# Schematic.net
KiCad netlist of a schematic drawn in Altium Designer
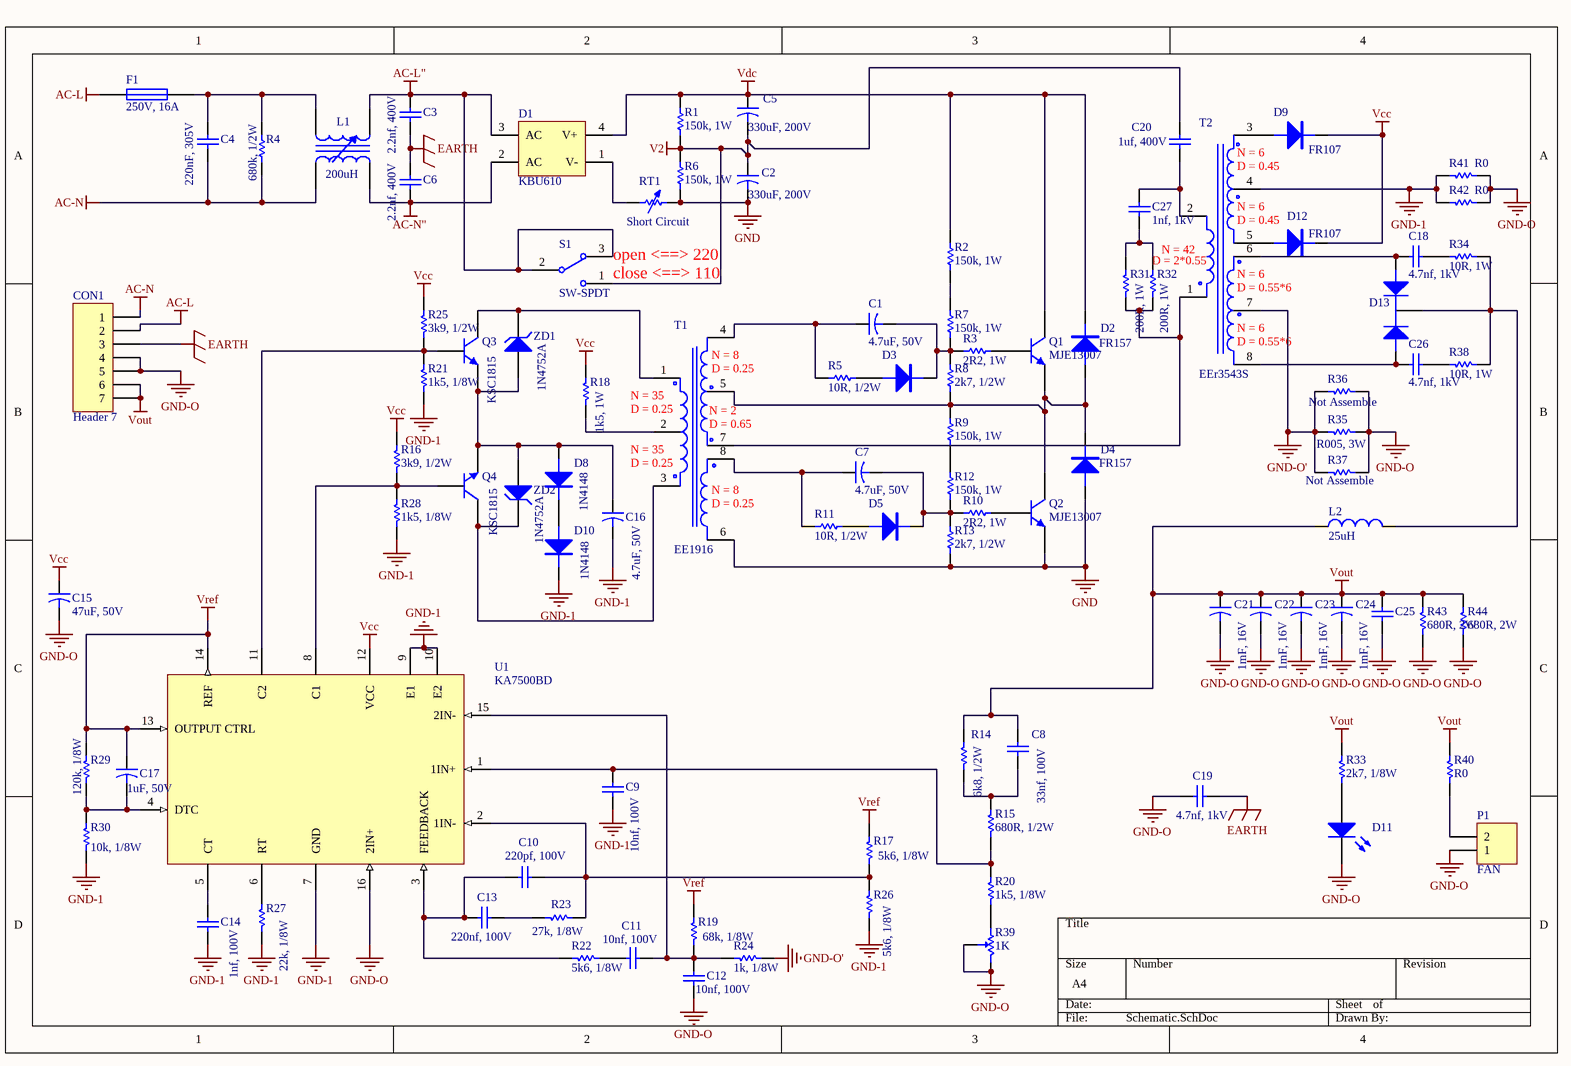
[diagram p0: Schematic.SchDoc]

(export (version "E")
  (design (tool "Eeschema 10.0.6"))
  (components
    (comp (ref "C1")
      (value "4.7uF, 50V")
      (footprint "CAP-P2.54-D6")
      (description "200V, 330uF")
      (libsource (lib "Miscellaneous Devices") (part "Cap2"))
    )
    (comp (ref "C2")
      (value "330uF, 200V")
      (footprint "C_EL_20X35")
      (description "200V, 330uF")
      (libsource (lib "Miscellaneous Devices") (part "Cap2"))
    )
    (comp (ref "C3")
      (value "2.2nf, 400V")
      (footprint "C_CER_D7C")
      (description "jn222m")
      (libsource (lib "Miscellaneous Devices") (part "Cap"))
    )
    (comp (ref "C4")
      (value "220nF, 305V")
      (footprint "CAP-pitch15")
      (description "mkp62 x2  224 k 305v")
      (libsource (lib "Miscellaneous Devices") (part "Cap"))
    )
    (comp (ref "C5")
      (value "330uF, 200V")
      (footprint "C_EL_20X35")
      (description "200V, 330uF")
      (libsource (lib "Miscellaneous Devices") (part "Cap2"))
    )
    (comp (ref "C6")
      (value "2.2nf, 400V")
      (footprint "C_CER_D7C")
      (description "jn222m")
      (libsource (lib "Miscellaneous Devices") (part "Cap"))
    )
    (comp (ref "C7")
      (value "4.7uF, 50V")
      (footprint "CAP-P2.54-D6")
      (description "200V, 330uF")
      (libsource (lib "Miscellaneous Devices") (part "Cap2"))
    )
    (comp (ref "C8")
      (value "33nf, 100V")
      (footprint "RAD0.2-1")
      (description "2A333j")
      (libsource (lib "Miscellaneous Devices") (part "Cap"))
    )
    (comp (ref "C9")
      (value "10nf, 100V")
      (footprint "RAD0.2-1")
      (description "2A103j")
      (libsource (lib "Miscellaneous Devices") (part "Cap"))
    )
    (comp (ref "C10")
      (value "220pf, 100V")
      (footprint "RAD0.2-1")
      (description "2A221j")
      (libsource (lib "Miscellaneous Devices") (part "Cap"))
    )
    (comp (ref "C11")
      (value "10nf, 100V")
      (footprint "RAD0.2-1")
      (description "2A103j")
      (libsource (lib "Miscellaneous Devices") (part "Cap"))
    )
    (comp (ref "C12")
      (value "10nf, 100V")
      (footprint "RAD0.2-1")
      (description "2A103j")
      (libsource (lib "Miscellaneous Devices") (part "Cap"))
    )
    (comp (ref "C13")
      (value "220nf, 100V")
      (footprint "RAD0.2-1")
      (description "2A223j")
      (libsource (lib "Miscellaneous Devices") (part "Cap"))
    )
    (comp (ref "C14")
      (value "1nf, 100V")
      (footprint "RAD0.2-1")
      (description "2A102j")
      (libsource (lib "Miscellaneous Devices") (part "Cap"))
    )
    (comp (ref "C15")
      (value "47uF, 50V")
      (footprint "CAP-P2.54-D6")
      (description "200V, 330uF")
      (libsource (lib "Miscellaneous Devices") (part "Cap2"))
    )
    (comp (ref "C16")
      (value "4.7uF, 50V")
      (footprint "CAP-P2.54-D6")
      (description "200V, 330uF")
      (libsource (lib "Miscellaneous Devices") (part "Cap2"))
    )
    (comp (ref "C17")
      (value "1uF, 50V")
      (footprint "CAP-P2.54-D6")
      (description "200V, 330uF")
      (libsource (lib "Miscellaneous Devices") (part "Cap2"))
    )
    (comp (ref "C18")
      (value "4.7nf, 1kV")
      (footprint "C_CER_D6B")
      (libsource (lib "Miscellaneous Devices") (part "Cap"))
    )
    (comp (ref "C19")
      (value "4.7nf, 1kV")
      (footprint "RAD0.2-1")
      (libsource (lib "Miscellaneous Devices") (part "Cap"))
    )
    (comp (ref "C20")
      (value "1uf, 400V")
      (footprint "C_PLY_22X7")
      (description "ceramic")
      (libsource (lib "Miscellaneous Devices") (part "Cap"))
    )
    (comp (ref "C21")
      (value "1mF, 16V")
      (footprint "RB.2/.6-2")
      (description "200V, 330uF")
      (libsource (lib "Miscellaneous Devices") (part "Cap2"))
    )
    (comp (ref "C22")
      (value "1mF, 16V")
      (footprint "RB.2/.6-2")
      (description "200V, 330uF")
      (libsource (lib "Miscellaneous Devices") (part "Cap2"))
    )
    (comp (ref "C23")
      (value "1mF, 16V")
      (footprint "RB.2/.6-2")
      (description "200V, 330uF")
      (libsource (lib "Miscellaneous Devices") (part "Cap2"))
    )
    (comp (ref "C24")
      (value "1mF, 16V")
      (footprint "RB.2/.6-2")
      (description "200V, 330uF")
      (libsource (lib "Miscellaneous Devices") (part "Cap2"))
    )
    (comp (ref "C25")
      (value "~")
      (footprint "C_CER_D6B")
      (libsource (lib "Miscellaneous Devices") (part "Cap"))
    )
    (comp (ref "C26")
      (value "4.7nf, 1kV")
      (footprint "C_CER_D6B")
      (libsource (lib "Miscellaneous Devices") (part "Cap"))
    )
    (comp (ref "C27")
      (value "1nf, 1kV")
      (footprint "C_CER_D6B")
      (libsource (lib "Miscellaneous Devices") (part "Cap"))
    )
    (comp (ref "CON1")
      (value "Header 7")
      (footprint "barrier-terminal-7P")
      (description "Header, 7-Pin")
      (fields (field (name "PUBLISHER") "Altium Limited"))
      (libsource (lib "Miscellaneous Connectors") (part "Header 7"))
    )
    (comp (ref "D1")
      (value "KBU610")
      (footprint "Diode-12")
      (description "35A, 1200V")
      (fields (field (name "MANUFACTURER") "HY Electronic"))
      (libsource (lib "JDEVS-SCH") (part "Bridge"))
    )
    (comp (ref "D2")
      (value "FR157")
      (footprint "D_AX05_DO15")
      (fields (field (name "MANUFACTURER") "Comchip Technology"))
      (libsource (lib "JDEVS-SCH") (part "DIODE5"))
    )
    (comp (ref "D3")
      (value "~")
      (footprint "D_AX04_DO41")
      (fields (field (name "MANUFACTURER") "Comchip Technology"))
      (libsource (lib "JDEVS-SCH") (part "DIODE5"))
    )
    (comp (ref "D4")
      (value "FR157")
      (footprint "D_AX05_DO15")
      (fields (field (name "MANUFACTURER") "Comchip Technology"))
      (libsource (lib "JDEVS-SCH") (part "DIODE5"))
    )
    (comp (ref "D5")
      (value "~")
      (footprint "D_AX04_DO41")
      (fields (field (name "MANUFACTURER") "Comchip Technology"))
      (libsource (lib "JDEVS-SCH") (part "DIODE5"))
    )
    (comp (ref "D8")
      (value "1N4148")
      (footprint "D_AX03_DO35")
      (fields (field (name "MANUFACTURER") "Comchip Technology"))
      (libsource (lib "JDEVS-SCH") (part "DIODE5"))
    )
    (comp (ref "D9")
      (value "FR107")
      (footprint "D_AX04_DO41")
      (fields (field (name "MANUFACTURER") "Comchip Technology"))
      (libsource (lib "JDEVS-SCH") (part "DIODE5"))
    )
    (comp (ref "D10")
      (value "1N4148")
      (footprint "D_AX03_DO35")
      (fields (field (name "MANUFACTURER") "Comchip Technology"))
      (libsource (lib "JDEVS-SCH") (part "DIODE5"))
    )
    (comp (ref "D11")
      (value "LED RED")
      (footprint "LED3MM")
      (description "Typical INFRARED GaAs LED")
      (libsource (lib "Miscellaneous Devices") (part "LED0"))
    )
    (comp (ref "D12")
      (value "FR107")
      (footprint "D_AX04_DO41")
      (fields (field (name "MANUFACTURER") "Comchip Technology"))
      (libsource (lib "JDEVS-SCH") (part "DIODE5"))
    )
    (comp (ref "D13")
      (value "MBR20200CT")
      (footprint "TO-220ne3")
      (fields (field (name "MANUFACTURER") "ON"))
      (libsource (lib "JDEVS-SCH") (part "Diode 3pin"))
    )
    (comp (ref "F1")
      (value "250V, 16A")
      (footprint "Fuse -10")
      (description "Fuse")
      (libsource (lib "Miscellaneous Devices") (part "Fuse 1"))
    )
    (comp (ref "L1")
      (value "200uH")
      (footprint "Trans-11")
      (fields (field (name "MANUFACTURER") "click"))
      (libsource (lib "Miscellaneous Devices") (part "Trans Adj"))
    )
    (comp (ref "L2")
      (value "25uH")
      (footprint "inductor-6")
      (description "260-04930-10E   082-10394-01    click      1929")
      (fields (field (name "MANUFACTURER") "click"))
      (libsource (lib "Miscellaneous Devices") (part "Inductor"))
    )
    (comp (ref "P1")
      (value "FAN")
      (footprint "XH_2")
      (description "Header, 2-Pin")
      (libsource (lib "Miscellaneous Connectors") (part "Header 2"))
    )
    (comp (ref "Q1")
      (value "MJE13007")
      (footprint "TO-220ne3")
      (fields (field (name "MANUFACTURER") "ON"))
      (libsource (lib "Miscellaneous Devices") (part "QNPN"))
    )
    (comp (ref "Q2")
      (value "MJE13007")
      (footprint "TO-220ne3")
      (fields (field (name "MANUFACTURER") "ON"))
      (libsource (lib "Miscellaneous Devices") (part "QNPN"))
    )
    (comp (ref "Q3")
      (value "KSC1815")
      (footprint "TO92_3B")
      (libsource (lib "Miscellaneous Devices") (part "QNPN"))
    )
    (comp (ref "Q4")
      (value "KSC1815")
      (footprint "TO92_3B")
      (libsource (lib "Miscellaneous Devices") (part "QNPN"))
    )
    (comp (ref "R1")
      (value "150k, 1W")
      (footprint "R05W_AX05")
      (description "Resistor")
      (libsource (lib "Miscellaneous Devices") (part "Res1"))
    )
    (comp (ref "R2")
      (value "150k, 1W")
      (footprint "R05W_AX05")
      (description "Resistor")
      (libsource (lib "Miscellaneous Devices") (part "Res1"))
    )
    (comp (ref "R3")
      (value "2R2, 1W")
      (footprint "R05W_AX05")
      (description "Resistor")
      (libsource (lib "Miscellaneous Devices") (part "Res1"))
    )
    (comp (ref "R4")
      (value "680k, 1/2W")
      (footprint "R05W_AX05")
      (description "Resistor")
      (libsource (lib "Miscellaneous Devices") (part "Res1"))
    )
    (comp (ref "R5")
      (value "10R, 1/2W")
      (footprint "R025W_AX04")
      (description "Resistor")
      (libsource (lib "Miscellaneous Devices") (part "Res1"))
    )
    (comp (ref "R6")
      (value "150k, 1W")
      (footprint "R05W_AX05")
      (description "Resistor")
      (libsource (lib "Miscellaneous Devices") (part "Res1"))
    )
    (comp (ref "R7")
      (value "150k, 1W")
      (footprint "R05W_AX05")
      (description "Resistor")
      (libsource (lib "Miscellaneous Devices") (part "Res1"))
    )
    (comp (ref "R8")
      (value "2k7, 1/2W")
      (footprint "R025W_AX04")
      (description "Resistor")
      (libsource (lib "Miscellaneous Devices") (part "Res1"))
    )
    (comp (ref "R9")
      (value "150k, 1W")
      (footprint "R05W_AX05")
      (description "Resistor")
      (libsource (lib "Miscellaneous Devices") (part "Res1"))
    )
    (comp (ref "R10")
      (value "2R2, 1W")
      (footprint "R05W_AX05")
      (description "Resistor")
      (libsource (lib "Miscellaneous Devices") (part "Res1"))
    )
    (comp (ref "R11")
      (value "10R, 1/2W")
      (footprint "R025W_AX04")
      (description "Resistor")
      (libsource (lib "Miscellaneous Devices") (part "Res1"))
    )
    (comp (ref "R12")
      (value "150k, 1W")
      (footprint "R05W_AX05")
      (description "Resistor")
      (libsource (lib "Miscellaneous Devices") (part "Res1"))
    )
    (comp (ref "R13")
      (value "2k7, 1/2W")
      (footprint "R025W_AX04")
      (description "Resistor")
      (libsource (lib "Miscellaneous Devices") (part "Res1"))
    )
    (comp (ref "R14")
      (value "6k8, 1/2W")
      (footprint "R025W_AX04")
      (description "Resistor")
      (libsource (lib "Miscellaneous Devices") (part "Res1"))
    )
    (comp (ref "R15")
      (value "680R, 1/2W")
      (footprint "R025W_AX04")
      (description "Resistor")
      (libsource (lib "Miscellaneous Devices") (part "Res1"))
    )
    (comp (ref "R16")
      (value "3k9, 1/2W")
      (footprint "R025W_AX04")
      (description "Resistor")
      (libsource (lib "Miscellaneous Devices") (part "Res1"))
    )
    (comp (ref "R17")
      (value "5k6, 1/8W")
      (footprint "R0125W_AX025")
      (description "Resistor")
      (libsource (lib "Miscellaneous Devices") (part "Res1"))
    )
    (comp (ref "R18")
      (value "1k5, 1W")
      (footprint "R05W_AX05")
      (description "Resistor")
      (libsource (lib "Miscellaneous Devices") (part "Res1"))
    )
    (comp (ref "R19")
      (value "68k, 1/8W")
      (footprint "R0125W_AX025")
      (description "Resistor")
      (libsource (lib "Miscellaneous Devices") (part "Res1"))
    )
    (comp (ref "R20")
      (value "1k5, 1/8W")
      (footprint "R0125W_AX025")
      (description "Resistor")
      (libsource (lib "Miscellaneous Devices") (part "Res1"))
    )
    (comp (ref "R21")
      (value "1k5, 1/8W")
      (footprint "R0125W_AX025")
      (description "Resistor")
      (libsource (lib "Miscellaneous Devices") (part "Res1"))
    )
    (comp (ref "R22")
      (value "5k6, 1/8W")
      (footprint "R0125W_AX025")
      (description "Resistor")
      (libsource (lib "Miscellaneous Devices") (part "Res1"))
    )
    (comp (ref "R23")
      (value "27k, 1/8W")
      (footprint "R0125W_AX025")
      (description "Resistor")
      (libsource (lib "Miscellaneous Devices") (part "Res1"))
    )
    (comp (ref "R24")
      (value "1k, 1/8W")
      (footprint "R0125W_AX025")
      (description "Resistor")
      (libsource (lib "Miscellaneous Devices") (part "Res1"))
    )
    (comp (ref "R25")
      (value "3k9, 1/2W")
      (footprint "R025W_AX04")
      (description "Resistor")
      (libsource (lib "Miscellaneous Devices") (part "Res1"))
    )
    (comp (ref "R26")
      (value "5k6, 1/8W")
      (footprint "R0125W_AX025")
      (description "Resistor")
      (libsource (lib "Miscellaneous Devices") (part "Res1"))
    )
    (comp (ref "R27")
      (value "22k, 1/8W")
      (footprint "R0125W_AX025")
      (description "Resistor")
      (libsource (lib "Miscellaneous Devices") (part "Res1"))
    )
    (comp (ref "R28")
      (value "1k5, 1/8W")
      (footprint "R0125W_AX025")
      (description "Resistor")
      (libsource (lib "Miscellaneous Devices") (part "Res1"))
    )
    (comp (ref "R29")
      (value "120k, 1/8W")
      (footprint "R0125W_AX025")
      (description "Resistor")
      (libsource (lib "Miscellaneous Devices") (part "Res1"))
    )
    (comp (ref "R30")
      (value "10k, 1/8W")
      (footprint "R0125W_AX025")
      (description "Resistor")
      (libsource (lib "Miscellaneous Devices") (part "Res1"))
    )
    (comp (ref "R31")
      (value "200R, 1W")
      (footprint "R1W_AX06")
      (description "Resistor")
      (libsource (lib "Miscellaneous Devices") (part "Res1"))
    )
    (comp (ref "R32")
      (value "200R, 1W")
      (footprint "R1W_AX06")
      (description "Resistor")
      (libsource (lib "Miscellaneous Devices") (part "Res1"))
    )
    (comp (ref "R33")
      (value "2k7, 1/8W")
      (footprint "R0125W_AX025")
      (description "Resistor")
      (libsource (lib "Miscellaneous Devices") (part "Res1"))
    )
    (comp (ref "R34")
      (value "10R, 1W")
      (footprint "R05W_AX05")
      (description "Resistor")
      (libsource (lib "Miscellaneous Devices") (part "Res1"))
    )
    (comp (ref "R35")
      (value "R005, 3W")
      (footprint "J10MM")
      (description "Resistor")
      (libsource (lib "Miscellaneous Devices") (part "Res1"))
    )
    (comp (ref "R36")
      (value "Not Assemble")
      (footprint "J10MM")
      (description "Resistor")
      (libsource (lib "Miscellaneous Devices") (part "Res1"))
    )
    (comp (ref "R37")
      (value "Not Assemble")
      (footprint "J10MM")
      (description "Resistor")
      (libsource (lib "Miscellaneous Devices") (part "Res1"))
    )
    (comp (ref "R38")
      (value "10R, 1W")
      (footprint "R05W_AX05")
      (description "Resistor")
      (libsource (lib "Miscellaneous Devices") (part "Res1"))
    )
    (comp (ref "R39")
      (value "1K")
      (footprint "Pot 00")
      (description "Variable Resistor")
      (fields (field (name "DESIGNER") "Saeid Jorablo"))
      (libsource (lib "My Library") (part "Resistor Variable"))
    )
    (comp (ref "R40")
      (value "R0")
      (footprint "J10MM")
      (description "Resistor")
      (libsource (lib "Miscellaneous Devices") (part "Res1"))
    )
    (comp (ref "R41")
      (value "R0")
      (footprint "J7P6MM")
      (description "Resistor")
      (libsource (lib "Miscellaneous Devices") (part "Res1"))
    )
    (comp (ref "R42")
      (value "R0")
      (footprint "J7P6MM")
      (description "Resistor")
      (libsource (lib "Miscellaneous Devices") (part "Res1"))
    )
    (comp (ref "R43")
      (value "680R, 2W")
      (footprint "R1W_AX06")
      (description "NA")
      (libsource (lib "Miscellaneous Devices") (part "Res1"))
    )
    (comp (ref "R44")
      (value "680R, 2W")
      (footprint "R1W_AX06")
      (description "Resistor")
      (libsource (lib "Miscellaneous Devices") (part "Res1"))
    )
    (comp (ref "RT1")
      (value "Short Circuit")
      (footprint "J7P6MM")
      (libsource (lib "Miscellaneous Devices") (part "Res Adj1"))
    )
    (comp (ref "S1")
      (value "SW-SPDT")
      (footprint "Switch - SPDT")
      (description "SPDT Subminiature Toggle Switch, Right Angle Mounting, Vertical Actuation")
      (fields (field (name "PUBLISHER") "Altium Limited"))
      (libsource (lib "Miscellaneous Devices") (part "SW-SPDT"))
    )
    (comp (ref "T1")
      (value "EE1916")
      (footprint "EE1916-3")
      (libsource (lib "JDEVS-SCH") (part "Transformers 78253 Series_1"))
    )
    (comp (ref "T2")
      (value "EEr3543S")
      (footprint "EFD30_12")
      (libsource (lib "JDEVS-SCH") (part "Transformers 78253 Series_2"))
    )
    (comp (ref "U1")
      (value "KA7500BD")
      (footprint "Dip-16pin")
      (description "TEXAS INSTRUMENTS - TL494CN - VOLTAGE MODE PWM CONTROLLER, 40V, 16-DIP")
      (fields
        (field (name "MANUFACTURER") "Texas Instruments")
        (field (name "MANUFACTURER PART NUMBER") "TL494CN")
      )
      (libsource (lib "JDEVS-SCH") (part "KA7500BD"))
    )
    (comp (ref "ZD1")
      (value "1N4752A")
      (footprint "Diode 1W")
      (description "25V Zener Diode")
      (libsource (lib "Miscellaneous Devices") (part "D Zener"))
    )
    (comp (ref "ZD2")
      (value "1N4752A")
      (footprint "Diode 1W")
      (description "25V Zener Diode")
      (libsource (lib "Miscellaneous Devices") (part "D Zener"))
    )
  )
  (nets
    (net (code "1") (name "AC-L") (class "Default")
      (node (ref "CON1") (pin "2") (pinfunction "2_2") (pintype "passive"))
      (node (ref "F1") (pin "2") (pinfunction "2_2") (pintype "passive"))
    )
    (net (code "2") (name "AC-L\"") (class "Default")
      (node (ref "C3") (pin "1") (pinfunction "1_1") (pintype "passive"))
      (node (ref "D1") (pin "3") (pinfunction "AC_3") (pintype "passive"))
      (node (ref "L1") (pin "2") (pinfunction "2_2") (pintype "passive"))
      (node (ref "S1") (pin "2") (pinfunction "2_2") (pintype "passive"))
      (node (ref "S1") (pin "3") (pinfunction "3_3") (pintype "passive"))
    )
    (net (code "3") (name "AC-N") (class "Default")
      (node (ref "C4") (pin "2") (pinfunction "2_2") (pintype "passive"))
      (node (ref "CON1") (pin "1") (pinfunction "1_1") (pintype "passive"))
      (node (ref "L1") (pin "1") (pinfunction "3_1") (pintype "passive"))
      (node (ref "R4") (pin "2") (pinfunction "2_2") (pintype "passive"))
    )
    (net (code "4") (name "AC-N\"") (class "Default")
      (node (ref "C6") (pin "2") (pinfunction "2_2") (pintype "passive"))
      (node (ref "D1") (pin "2") (pinfunction "AC_2") (pintype "passive"))
      (node (ref "L1") (pin "3") (pinfunction "1_3") (pintype "passive"))
    )
    (net (code "5") (name "EARTH") (class "Default")
      (node (ref "C19") (pin "2") (pinfunction "2_2") (pintype "passive"))
      (node (ref "C3") (pin "2") (pinfunction "2_2") (pintype "passive"))
      (node (ref "C6") (pin "1") (pinfunction "1_1") (pintype "passive"))
      (node (ref "CON1") (pin "3") (pinfunction "3_3") (pintype "passive"))
    )
    (net (code "6") (name "GND") (class "Default")
      (node (ref "C2") (pin "2") (pinfunction "2_2") (pintype "passive"))
      (node (ref "D4") (pin "1") (pinfunction "1_1") (pintype "passive"))
      (node (ref "Q2") (pin "1") (pinfunction "E_1") (pintype "passive"))
      (node (ref "R13") (pin "2") (pinfunction "2_2") (pintype "passive"))
      (node (ref "R6") (pin "2") (pinfunction "2_2") (pintype "passive"))
      (node (ref "RT1") (pin "2") (pinfunction "2_2") (pintype "passive"))
      (node (ref "T1") (pin "6") (pinfunction "6_6") (pintype "passive"))
    )
    (net (code "7") (name "GND-1") (class "Default")
      (node (ref "C14") (pin "2") (pinfunction "2_2") (pintype "passive"))
      (node (ref "C16") (pin "2") (pinfunction "2_2") (pintype "passive"))
      (node (ref "C9") (pin "2") (pinfunction "2_2") (pintype "passive"))
      (node (ref "D10") (pin "2") (pinfunction "2_2") (pintype "passive"))
      (node (ref "R21") (pin "2") (pinfunction "2_2") (pintype "passive"))
      (node (ref "R26") (pin "2") (pinfunction "2_2") (pintype "passive"))
      (node (ref "R27") (pin "2") (pinfunction "2_2") (pintype "passive"))
      (node (ref "R28") (pin "2") (pinfunction "2_2") (pintype "passive"))
      (node (ref "R30") (pin "2") (pinfunction "2_2") (pintype "passive"))
      (node (ref "R41") (pin "2") (pinfunction "2_2") (pintype "passive"))
      (node (ref "R42") (pin "2") (pinfunction "2_2") (pintype "passive"))
      (node (ref "T2") (pin "4") (pinfunction "4_4") (pintype "passive"))
      (node (ref "U1") (pin "10") (pinfunction "E2_10") (pintype "passive"))
      (node (ref "U1") (pin "7") (pinfunction "GND_7") (pintype "power_in"))
      (node (ref "U1") (pin "9") (pinfunction "E1_9") (pintype "passive"))
    )
    (net (code "8") (name "GND-O") (class "Default")
      (node (ref "C12") (pin "1") (pinfunction "1_1") (pintype "passive"))
      (node (ref "C15") (pin "2") (pinfunction "2_2") (pintype "passive"))
      (node (ref "C19") (pin "1") (pinfunction "1_1") (pintype "passive"))
      (node (ref "C21") (pin "2") (pinfunction "2_2") (pintype "passive"))
      (node (ref "C22") (pin "2") (pinfunction "2_2") (pintype "passive"))
      (node (ref "C23") (pin "2") (pinfunction "2_2") (pintype "passive"))
      (node (ref "C24") (pin "2") (pinfunction "2_2") (pintype "passive"))
      (node (ref "C25") (pin "2") (pinfunction "2_2") (pintype "passive"))
      (node (ref "CON1") (pin "4") (pinfunction "4_4") (pintype "passive"))
      (node (ref "CON1") (pin "5") (pinfunction "5_5") (pintype "passive"))
      (node (ref "D11") (pin "2") (pinfunction "K_2") (pintype "passive"))
      (node (ref "P1") (pin "1") (pinfunction "1_1") (pintype "passive"))
      (node (ref "R35") (pin "2") (pinfunction "2_2") (pintype "passive"))
      (node (ref "R36") (pin "1") (pinfunction "1_1") (pintype "passive"))
      (node (ref "R37") (pin "2") (pinfunction "2_2") (pintype "passive"))
      (node (ref "R39") (pin "1") (pinfunction "CCW_1") (pintype "passive"))
      (node (ref "R39") (pin "3") (pinfunction "Setpoint_3") (pintype "passive"))
      (node (ref "R41") (pin "1") (pinfunction "1_1") (pintype "passive"))
      (node (ref "R42") (pin "1") (pinfunction "1_1") (pintype "passive"))
      (node (ref "R43") (pin "1") (pinfunction "1_1") (pintype "passive"))
      (node (ref "R44") (pin "1") (pinfunction "1_1") (pintype "passive"))
      (node (ref "U1") (pin "16") (pinfunction "2IN+_16") (pintype "input"))
    )
    (net (code "9") (name "GND-O'") (class "Default")
      (node (ref "R24") (pin "2") (pinfunction "2_2") (pintype "passive"))
      (node (ref "R35") (pin "1") (pinfunction "1_1") (pintype "passive"))
      (node (ref "R36") (pin "2") (pinfunction "2_2") (pintype "passive"))
      (node (ref "R37") (pin "1") (pinfunction "1_1") (pintype "passive"))
      (node (ref "T2") (pin "7") (pinfunction "7_7") (pintype "passive"))
    )
    (net (code "10") (name "Net-(C1-Pad1)") (class "Default")
      (node (ref "C1") (pin "1") (pinfunction "1_1") (pintype "passive"))
      (node (ref "R5") (pin "2") (pinfunction "2_2") (pintype "passive"))
      (node (ref "T1") (pin "4") (pinfunction "4_4") (pintype "passive"))
    )
    (net (code "11") (name "Net-(C1-Pad2)") (class "Default")
      (node (ref "C1") (pin "2") (pinfunction "2_2") (pintype "passive"))
      (node (ref "D3") (pin "2") (pinfunction "2_2") (pintype "passive"))
      (node (ref "R3") (pin "2") (pinfunction "2_2") (pintype "passive"))
      (node (ref "R7") (pin "2") (pinfunction "2_2") (pintype "passive"))
      (node (ref "R8") (pin "1") (pinfunction "1_1") (pintype "passive"))
    )
    (net (code "12") (name "Net-(C4-Pad1)") (class "Default")
      (node (ref "C4") (pin "1") (pinfunction "1_1") (pintype "passive"))
      (node (ref "F1") (pin "1") (pinfunction "1_1") (pintype "passive"))
      (node (ref "L1") (pin "4") (pinfunction "4_4") (pintype "passive"))
      (node (ref "R4") (pin "1") (pinfunction "1_1") (pintype "passive"))
    )
    (net (code "13") (name "Net-(C7-Pad1)") (class "Default")
      (node (ref "C7") (pin "1") (pinfunction "1_1") (pintype "passive"))
      (node (ref "R11") (pin "2") (pinfunction "2_2") (pintype "passive"))
      (node (ref "T1") (pin "8") (pinfunction "8_8") (pintype "passive"))
    )
    (net (code "14") (name "Net-(C7-Pad2)") (class "Default")
      (node (ref "C7") (pin "2") (pinfunction "2_2") (pintype "passive"))
      (node (ref "D5") (pin "2") (pinfunction "2_2") (pintype "passive"))
      (node (ref "R10") (pin "2") (pinfunction "2_2") (pintype "passive"))
      (node (ref "R12") (pin "2") (pinfunction "2_2") (pintype "passive"))
      (node (ref "R13") (pin "1") (pinfunction "1_1") (pintype "passive"))
    )
    (net (code "15") (name "Net-(C8-Pad2)") (class "Default")
      (node (ref "C8") (pin "2") (pinfunction "2_2") (pintype "passive"))
      (node (ref "R14") (pin "2") (pinfunction "2_2") (pintype "passive"))
      (node (ref "R15") (pin "1") (pinfunction "1_1") (pintype "passive"))
    )
    (net (code "16") (name "Net-(C11-Pad1)") (class "Default")
      (node (ref "C11") (pin "1") (pinfunction "1_1") (pintype "passive"))
      (node (ref "R22") (pin "2") (pinfunction "2_2") (pintype "passive"))
    )
    (net (code "17") (name "Net-(C13-Pad2)") (class "Default")
      (node (ref "C13") (pin "2") (pinfunction "2_2") (pintype "passive"))
      (node (ref "R23") (pin "1") (pinfunction "1_1") (pintype "passive"))
    )
    (net (code "18") (name "Net-(C18-Pad1)") (class "Default")
      (node (ref "C18") (pin "1") (pinfunction "1_1") (pintype "passive"))
      (node (ref "R34") (pin "2") (pinfunction "2_2") (pintype "passive"))
    )
    (net (code "19") (name "Net-(C18-Pad2)") (class "Default")
      (node (ref "C18") (pin "2") (pinfunction "2_2") (pintype "passive"))
      (node (ref "D13") (pin "3") (pinfunction "3_3") (pintype "passive"))
      (node (ref "T2") (pin "6") (pinfunction "6_6") (pintype "passive"))
    )
    (net (code "20") (name "Net-(C20-Pad2)") (class "Default")
      (node (ref "C20") (pin "2") (pinfunction "2_2") (pintype "passive"))
      (node (ref "C27") (pin "1") (pinfunction "1_1") (pintype "passive"))
      (node (ref "T2") (pin "2") (pinfunction "2_2") (pintype "passive"))
    )
    (net (code "21") (name "Net-(C26-Pad1)") (class "Default")
      (node (ref "C26") (pin "1") (pinfunction "1_1") (pintype "passive"))
      (node (ref "D13") (pin "1") (pinfunction "1_1") (pintype "passive"))
      (node (ref "T2") (pin "8") (pinfunction "8_8") (pintype "passive"))
    )
    (net (code "22") (name "Net-(C26-Pad2)") (class "Default")
      (node (ref "C26") (pin "2") (pinfunction "2_2") (pintype "passive"))
      (node (ref "R38") (pin "2") (pinfunction "2_2") (pintype "passive"))
    )
    (net (code "23") (name "Net-(C27-Pad2)") (class "Default")
      (node (ref "C27") (pin "2") (pinfunction "2_2") (pintype "passive"))
      (node (ref "R31") (pin "2") (pinfunction "2_2") (pintype "passive"))
      (node (ref "R32") (pin "2") (pinfunction "2_2") (pintype "passive"))
    )
    (net (code "24") (name "Net-(D1-V-)") (class "Default")
      (node (ref "D1") (pin "1") (pinfunction "V-_1") (pintype "passive"))
      (node (ref "RT1") (pin "1") (pinfunction "1_1") (pintype "passive"))
    )
    (net (code "25") (name "Net-(D3-Pad1)") (class "Default")
      (node (ref "D3") (pin "1") (pinfunction "1_1") (pintype "passive"))
      (node (ref "R5") (pin "1") (pinfunction "1_1") (pintype "passive"))
    )
    (net (code "26") (name "Net-(D5-Pad1)") (class "Default")
      (node (ref "D5") (pin "1") (pinfunction "1_1") (pintype "passive"))
      (node (ref "R11") (pin "1") (pinfunction "1_1") (pintype "passive"))
    )
    (net (code "27") (name "Net-(D9-Pad1)") (class "Default")
      (node (ref "D9") (pin "1") (pinfunction "1_1") (pintype "passive"))
      (node (ref "T2") (pin "3") (pinfunction "3_3") (pintype "passive"))
    )
    (net (code "28") (name "Net-(D10-Pad1)") (class "Default")
      (node (ref "D10") (pin "1") (pinfunction "1_1") (pintype "passive"))
      (node (ref "D8") (pin "2") (pinfunction "2_2") (pintype "passive"))
    )
    (net (code "29") (name "Net-(D11-A)") (class "Default")
      (node (ref "D11") (pin "1") (pinfunction "A_1") (pintype "passive"))
      (node (ref "R33") (pin "2") (pinfunction "2_2") (pintype "passive"))
    )
    (net (code "30") (name "Net-(D12-Pad1)") (class "Default")
      (node (ref "D12") (pin "1") (pinfunction "1_1") (pintype "passive"))
      (node (ref "T2") (pin "5") (pinfunction "5_5") (pintype "passive"))
    )
    (net (code "31") (name "Net-(D13-Pad2)") (class "Default")
      (node (ref "D13") (pin "2") (pinfunction "2_2") (pintype "passive"))
      (node (ref "L2") (pin "2") (pinfunction "2_2") (pintype "passive"))
      (node (ref "R34") (pin "1") (pinfunction "1_1") (pintype "passive"))
      (node (ref "R38") (pin "1") (pinfunction "1_1") (pintype "passive"))
    )
    (net (code "32") (name "Net-(P1-Pad2)") (class "Default")
      (node (ref "P1") (pin "2") (pinfunction "2_2") (pintype "passive"))
      (node (ref "R40") (pin "1") (pinfunction "1_1") (pintype "passive"))
    )
    (net (code "33") (name "Net-(Q1-B)") (class "Default")
      (node (ref "Q1") (pin "3") (pinfunction "B_3") (pintype "passive"))
      (node (ref "R3") (pin "1") (pinfunction "1_1") (pintype "passive"))
    )
    (net (code "34") (name "Net-(Q1-E)") (class "Default")
      (node (ref "D2") (pin "1") (pinfunction "1_1") (pintype "passive"))
      (node (ref "D4") (pin "2") (pinfunction "2_2") (pintype "passive"))
      (node (ref "Q1") (pin "1") (pinfunction "E_1") (pintype "passive"))
      (node (ref "Q2") (pin "2") (pinfunction "C_2") (pintype "passive"))
      (node (ref "R8") (pin "2") (pinfunction "2_2") (pintype "passive"))
      (node (ref "R9") (pin "1") (pinfunction "1_1") (pintype "passive"))
      (node (ref "T1") (pin "5") (pinfunction "5_5") (pintype "passive"))
    )
    (net (code "35") (name "Net-(Q2-B)") (class "Default")
      (node (ref "Q2") (pin "3") (pinfunction "B_3") (pintype "passive"))
      (node (ref "R10") (pin "1") (pinfunction "1_1") (pintype "passive"))
    )
    (net (code "36") (name "Net-(Q3-B)") (class "Default")
      (node (ref "Q3") (pin "3") (pinfunction "B_3") (pintype "passive"))
      (node (ref "R21") (pin "1") (pinfunction "1_1") (pintype "passive"))
      (node (ref "R25") (pin "2") (pinfunction "2_2") (pintype "passive"))
      (node (ref "U1") (pin "11") (pinfunction "C2_11") (pintype "passive"))
    )
    (net (code "37") (name "Net-(Q3-C)") (class "Default")
      (node (ref "Q3") (pin "2") (pinfunction "C_2") (pintype "passive"))
      (node (ref "T1") (pin "1") (pinfunction "1_1") (pintype "passive"))
      (node (ref "ZD1") (pin "2") (pinfunction "K_2") (pintype "passive"))
    )
    (net (code "38") (name "Net-(Q3-E)") (class "Default")
      (node (ref "C16") (pin "1") (pinfunction "1_1") (pintype "passive"))
      (node (ref "D8") (pin "1") (pinfunction "1_1") (pintype "passive"))
      (node (ref "Q3") (pin "1") (pinfunction "E_1") (pintype "passive"))
      (node (ref "Q4") (pin "1") (pinfunction "E_1") (pintype "passive"))
      (node (ref "ZD1") (pin "1") (pinfunction "A_1") (pintype "passive"))
      (node (ref "ZD2") (pin "1") (pinfunction "A_1") (pintype "passive"))
    )
    (net (code "39") (name "Net-(Q4-B)") (class "Default")
      (node (ref "Q4") (pin "3") (pinfunction "B_3") (pintype "passive"))
      (node (ref "R16") (pin "2") (pinfunction "2_2") (pintype "passive"))
      (node (ref "R28") (pin "1") (pinfunction "1_1") (pintype "passive"))
      (node (ref "U1") (pin "8") (pinfunction "C1_8") (pintype "passive"))
    )
    (net (code "40") (name "Net-(Q4-C)") (class "Default")
      (node (ref "Q4") (pin "2") (pinfunction "C_2") (pintype "passive"))
      (node (ref "T1") (pin "3") (pinfunction "3_3") (pintype "passive"))
      (node (ref "ZD2") (pin "2") (pinfunction "K_2") (pintype "passive"))
    )
    (net (code "41") (name "Net-(R2-Pad2)") (class "Default")
      (node (ref "R2") (pin "2") (pinfunction "2_2") (pintype "passive"))
      (node (ref "R7") (pin "1") (pinfunction "1_1") (pintype "passive"))
    )
    (net (code "42") (name "Net-(R12-Pad1)") (class "Default")
      (node (ref "R12") (pin "1") (pinfunction "1_1") (pintype "passive"))
      (node (ref "R9") (pin "2") (pinfunction "2_2") (pintype "passive"))
    )
    (net (code "43") (name "Net-(R18-Pad1)") (class "Default")
      (node (ref "R18") (pin "1") (pinfunction "1_1") (pintype "passive"))
      (node (ref "T1") (pin "2") (pinfunction "2_2") (pintype "passive"))
    )
    (net (code "44") (name "Net-(R31-Pad1)") (class "Default")
      (node (ref "R31") (pin "1") (pinfunction "1_1") (pintype "passive"))
      (node (ref "R32") (pin "1") (pinfunction "1_1") (pintype "passive"))
      (node (ref "T1") (pin "7") (pinfunction "7_7") (pintype "passive"))
      (node (ref "T2") (pin "1") (pinfunction "1_1") (pintype "passive"))
    )
    (net (code "45") (name "Net-(R39-CW)") (class "Default")
      (node (ref "R20") (pin "1") (pinfunction "1_1") (pintype "passive"))
      (node (ref "R39") (pin "2") (pinfunction "CW_2") (pintype "passive"))
    )
    (net (code "46") (name "Net-(U1-1IN+)") (class "Default")
      (node (ref "C9") (pin "1") (pinfunction "1_1") (pintype "passive"))
      (node (ref "R15") (pin "2") (pinfunction "2_2") (pintype "passive"))
      (node (ref "R20") (pin "2") (pinfunction "2_2") (pintype "passive"))
      (node (ref "U1") (pin "1") (pinfunction "1IN+_1") (pintype "input"))
    )
    (net (code "47") (name "Net-(U1-1IN-)") (class "Default")
      (node (ref "C10") (pin "2") (pinfunction "2_2") (pintype "passive"))
      (node (ref "R17") (pin "2") (pinfunction "2_2") (pintype "passive"))
      (node (ref "R23") (pin "2") (pinfunction "2_2") (pintype "passive"))
      (node (ref "R26") (pin "1") (pinfunction "1_1") (pintype "passive"))
      (node (ref "U1") (pin "2") (pinfunction "1IN-_2") (pintype "input"))
    )
    (net (code "48") (name "Net-(U1-2IN-)") (class "Default")
      (node (ref "C11") (pin "2") (pinfunction "2_2") (pintype "passive"))
      (node (ref "C12") (pin "2") (pinfunction "2_2") (pintype "passive"))
      (node (ref "R19") (pin "2") (pinfunction "2_2") (pintype "passive"))
      (node (ref "R24") (pin "1") (pinfunction "1_1") (pintype "passive"))
      (node (ref "U1") (pin "15") (pinfunction "2IN-_15") (pintype "input"))
    )
    (net (code "49") (name "Net-(U1-CT)") (class "Default")
      (node (ref "C14") (pin "1") (pinfunction "1_1") (pintype "passive"))
      (node (ref "U1") (pin "5") (pinfunction "CT_5") (pintype "passive"))
    )
    (net (code "50") (name "Net-(U1-DTC)") (class "Default")
      (node (ref "C17") (pin "2") (pinfunction "2_2") (pintype "passive"))
      (node (ref "R29") (pin "1") (pinfunction "1_1") (pintype "passive"))
      (node (ref "R30") (pin "1") (pinfunction "1_1") (pintype "passive"))
      (node (ref "U1") (pin "4") (pinfunction "DTC_4") (pintype "input"))
    )
    (net (code "51") (name "Net-(U1-FEEDBACK)") (class "Default")
      (node (ref "C10") (pin "1") (pinfunction "1_1") (pintype "passive"))
      (node (ref "C13") (pin "1") (pinfunction "1_1") (pintype "passive"))
      (node (ref "R22") (pin "1") (pinfunction "1_1") (pintype "passive"))
      (node (ref "U1") (pin "3") (pinfunction "FEEDBACK_3") (pintype "input"))
    )
    (net (code "52") (name "Net-(U1-RT)") (class "Default")
      (node (ref "R27") (pin "1") (pinfunction "1_1") (pintype "passive"))
      (node (ref "U1") (pin "6") (pinfunction "RT_6") (pintype "passive"))
    )
    (net (code "53") (name "V2") (class "Default")
      (node (ref "C2") (pin "1") (pinfunction "1_1") (pintype "passive"))
      (node (ref "C20") (pin "1") (pinfunction "1_1") (pintype "passive"))
      (node (ref "C5") (pin "2") (pinfunction "2_2") (pintype "passive"))
      (node (ref "R1") (pin "2") (pinfunction "2_2") (pintype "passive"))
      (node (ref "R6") (pin "1") (pinfunction "1_1") (pintype "passive"))
      (node (ref "S1") (pin "1") (pinfunction "1_1") (pintype "passive"))
    )
    (net (code "54") (name "Vcc") (class "Default")
      (node (ref "C15") (pin "1") (pinfunction "1_1") (pintype "passive"))
      (node (ref "D12") (pin "2") (pinfunction "2_2") (pintype "passive"))
      (node (ref "D9") (pin "2") (pinfunction "2_2") (pintype "passive"))
      (node (ref "R16") (pin "1") (pinfunction "1_1") (pintype "passive"))
      (node (ref "R18") (pin "2") (pinfunction "2_2") (pintype "passive"))
      (node (ref "R25") (pin "1") (pinfunction "1_1") (pintype "passive"))
      (node (ref "U1") (pin "12") (pinfunction "VCC_12") (pintype "power_in"))
    )
    (net (code "55") (name "Vdc") (class "Default")
      (node (ref "C5") (pin "1") (pinfunction "1_1") (pintype "passive"))
      (node (ref "D1") (pin "4") (pinfunction "V+_4") (pintype "passive"))
      (node (ref "D2") (pin "2") (pinfunction "2_2") (pintype "passive"))
      (node (ref "Q1") (pin "2") (pinfunction "C_2") (pintype "passive"))
      (node (ref "R1") (pin "1") (pinfunction "1_1") (pintype "passive"))
      (node (ref "R2") (pin "1") (pinfunction "1_1") (pintype "passive"))
    )
    (net (code "56") (name "Vout") (class "Default")
      (node (ref "C21") (pin "1") (pinfunction "1_1") (pintype "passive"))
      (node (ref "C22") (pin "1") (pinfunction "1_1") (pintype "passive"))
      (node (ref "C23") (pin "1") (pinfunction "1_1") (pintype "passive"))
      (node (ref "C24") (pin "1") (pinfunction "1_1") (pintype "passive"))
      (node (ref "C25") (pin "1") (pinfunction "1_1") (pintype "passive"))
      (node (ref "C8") (pin "1") (pinfunction "1_1") (pintype "passive"))
      (node (ref "CON1") (pin "6") (pinfunction "6_6") (pintype "passive"))
      (node (ref "CON1") (pin "7") (pinfunction "7_7") (pintype "passive"))
      (node (ref "L2") (pin "1") (pinfunction "1_1") (pintype "passive"))
      (node (ref "R14") (pin "1") (pinfunction "1_1") (pintype "passive"))
      (node (ref "R33") (pin "1") (pinfunction "1_1") (pintype "passive"))
      (node (ref "R40") (pin "2") (pinfunction "2_2") (pintype "passive"))
      (node (ref "R43") (pin "2") (pinfunction "2_2") (pintype "passive"))
      (node (ref "R44") (pin "2") (pinfunction "2_2") (pintype "passive"))
    )
    (net (code "57") (name "Vref") (class "Default")
      (node (ref "C17") (pin "1") (pinfunction "1_1") (pintype "passive"))
      (node (ref "R17") (pin "1") (pinfunction "1_1") (pintype "passive"))
      (node (ref "R19") (pin "1") (pinfunction "1_1") (pintype "passive"))
      (node (ref "R29") (pin "2") (pinfunction "2_2") (pintype "passive"))
      (node (ref "U1") (pin "13") (pinfunction "OUTPUT_CTRL_13") (pintype "input"))
      (node (ref "U1") (pin "14") (pinfunction "REF_14") (pintype "output"))
    )
  )
)
